# Display.net
KiCad netlist of a schematic drawn in Altium Designer
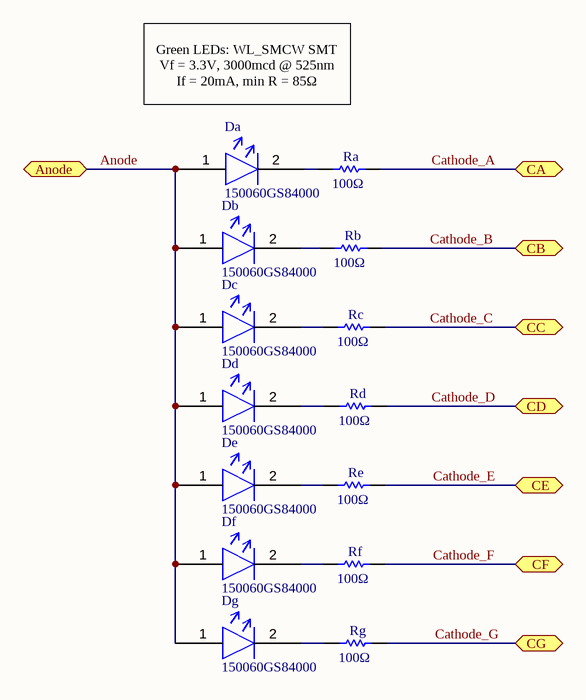
[diagram p0: Display.SchDoc]

(export (version "E")
  (design (tool "Eeschema 10.0.6"))
  (components
    (comp (ref "Da")
      (value "150060GS84000")
      (footprint "DIOC2408X10N")
      (description "Wl-smcw SMT Mono-color Chip Led")
      (libsource (lib "UConn Formula SAE") (part "150060GS84000-Symbol-1"))
    )
    (comp (ref "Db")
      (value "150060GS84000")
      (footprint "DIOC2408X10N")
      (description "Wl-smcw SMT Mono-color Chip Led")
      (libsource (lib "UConn Formula SAE") (part "150060GS84000-Symbol-1"))
    )
    (comp (ref "Dc")
      (value "150060GS84000")
      (footprint "DIOC2408X10N")
      (description "Wl-smcw SMT Mono-color Chip Led")
      (libsource (lib "UConn Formula SAE") (part "150060GS84000-Symbol-1"))
    )
    (comp (ref "Dd")
      (value "150060GS84000")
      (footprint "DIOC2408X10N")
      (description "Wl-smcw SMT Mono-color Chip Led")
      (libsource (lib "UConn Formula SAE") (part "150060GS84000-Symbol-1"))
    )
    (comp (ref "De")
      (value "150060GS84000")
      (footprint "DIOC2408X10N")
      (description "Wl-smcw SMT Mono-color Chip Led")
      (libsource (lib "UConn Formula SAE") (part "150060GS84000-Symbol-1"))
    )
    (comp (ref "Df")
      (value "150060GS84000")
      (footprint "DIOC2408X10N")
      (description "Wl-smcw SMT Mono-color Chip Led")
      (libsource (lib "UConn Formula SAE") (part "150060GS84000-Symbol-1"))
    )
    (comp (ref "Dg")
      (value "150060GS84000")
      (footprint "DIOC2408X10N")
      (description "Wl-smcw SMT Mono-color Chip Led")
      (libsource (lib "UConn Formula SAE") (part "150060GS84000-Symbol-1"))
    )
    (comp (ref "Ra")
      (value "100Ω")
      (footprint "RESC1005X40X25NL05T10")
      (fields (field (name "MANUFACTURER") "Yageo") (field (name "PART NUMBER") "RC0402FR-13100RL"))
      (libsource (lib "Altium Content Vault") (part "RES"))
    )
    (comp (ref "Rb")
      (value "100Ω")
      (footprint "RESC1005X40X25NL05T10")
      (fields (field (name "MANUFACTURER") "Yageo") (field (name "PART NUMBER") "RC0402FR-13100RL"))
      (libsource (lib "Altium Content Vault") (part "RES"))
    )
    (comp (ref "Rc")
      (value "100Ω")
      (footprint "RESC1005X40X25NL05T10")
      (fields (field (name "MANUFACTURER") "Yageo") (field (name "PART NUMBER") "RC0402FR-13100RL"))
      (libsource (lib "Altium Content Vault") (part "RES"))
    )
    (comp (ref "Rd")
      (value "100Ω")
      (footprint "RESC1005X40X25NL05T10")
      (fields (field (name "MANUFACTURER") "Yageo") (field (name "PART NUMBER") "RC0402FR-13100RL"))
      (libsource (lib "Altium Content Vault") (part "RES"))
    )
    (comp (ref "Re")
      (value "100Ω")
      (footprint "RESC1005X40X25NL05T10")
      (fields (field (name "MANUFACTURER") "Yageo") (field (name "PART NUMBER") "RC0402FR-13100RL"))
      (libsource (lib "Altium Content Vault") (part "RES"))
    )
    (comp (ref "Rf")
      (value "100Ω")
      (footprint "RESC1005X40X25NL05T10")
      (fields (field (name "MANUFACTURER") "Yageo") (field (name "PART NUMBER") "RC0402FR-13100RL"))
      (libsource (lib "Altium Content Vault") (part "RES"))
    )
    (comp (ref "Rg")
      (value "100Ω")
      (footprint "RESC1005X40X25NL05T10")
      (fields (field (name "MANUFACTURER") "Yageo") (field (name "PART NUMBER") "RC0402FR-13100RL"))
      (libsource (lib "Altium Content Vault") (part "RES"))
    )
  )
  (nets
    (net (code "1") (name "/Anode") (class "Default")
      (node (ref "Da") (pin "1") (pinfunction "+_1") (pintype "passive"))
      (node (ref "Db") (pin "1") (pinfunction "+_1") (pintype "passive"))
      (node (ref "Dc") (pin "1") (pinfunction "+_1") (pintype "passive"))
      (node (ref "Dd") (pin "1") (pinfunction "+_1") (pintype "passive"))
      (node (ref "De") (pin "1") (pinfunction "+_1") (pintype "passive"))
      (node (ref "Df") (pin "1") (pinfunction "+_1") (pintype "passive"))
      (node (ref "Dg") (pin "1") (pinfunction "+_1") (pintype "passive"))
    )
    (net (code "2") (name "/Cathode_A") (class "Default")
      (node (ref "Ra") (pin "2") (pinfunction "2_2") (pintype "passive"))
    )
    (net (code "3") (name "/Cathode_B") (class "Default")
      (node (ref "Rb") (pin "2") (pinfunction "2_2") (pintype "passive"))
    )
    (net (code "4") (name "/Cathode_C") (class "Default")
      (node (ref "Rc") (pin "2") (pinfunction "2_2") (pintype "passive"))
    )
    (net (code "5") (name "/Cathode_D") (class "Default")
      (node (ref "Rd") (pin "2") (pinfunction "2_2") (pintype "passive"))
    )
    (net (code "6") (name "/Cathode_E") (class "Default")
      (node (ref "Re") (pin "2") (pinfunction "2_2") (pintype "passive"))
    )
    (net (code "7") (name "/Cathode_F") (class "Default")
      (node (ref "Rf") (pin "2") (pinfunction "2_2") (pintype "passive"))
    )
    (net (code "8") (name "/Cathode_G") (class "Default")
      (node (ref "Rg") (pin "2") (pinfunction "2_2") (pintype "passive"))
    )
    (net (code "9") (name "Net-(Da--)") (class "Default")
      (node (ref "Da") (pin "2") (pinfunction "-_2") (pintype "passive"))
      (node (ref "Ra") (pin "1") (pinfunction "1_1") (pintype "passive"))
    )
    (net (code "10") (name "Net-(Db--)") (class "Default")
      (node (ref "Db") (pin "2") (pinfunction "-_2") (pintype "passive"))
      (node (ref "Rb") (pin "1") (pinfunction "1_1") (pintype "passive"))
    )
    (net (code "11") (name "Net-(Dc--)") (class "Default")
      (node (ref "Dc") (pin "2") (pinfunction "-_2") (pintype "passive"))
      (node (ref "Rc") (pin "1") (pinfunction "1_1") (pintype "passive"))
    )
    (net (code "12") (name "Net-(Dd--)") (class "Default")
      (node (ref "Dd") (pin "2") (pinfunction "-_2") (pintype "passive"))
      (node (ref "Rd") (pin "1") (pinfunction "1_1") (pintype "passive"))
    )
    (net (code "13") (name "Net-(De--)") (class "Default")
      (node (ref "De") (pin "2") (pinfunction "-_2") (pintype "passive"))
      (node (ref "Re") (pin "1") (pinfunction "1_1") (pintype "passive"))
    )
    (net (code "14") (name "Net-(Df--)") (class "Default")
      (node (ref "Df") (pin "2") (pinfunction "-_2") (pintype "passive"))
      (node (ref "Rf") (pin "1") (pinfunction "1_1") (pintype "passive"))
    )
    (net (code "15") (name "Net-(Dg--)") (class "Default")
      (node (ref "Dg") (pin "2") (pinfunction "-_2") (pintype "passive"))
      (node (ref "Rg") (pin "1") (pinfunction "1_1") (pintype "passive"))
    )
  )
)
